# Main.net
KiCad netlist of a schematic drawn in Altium Designer
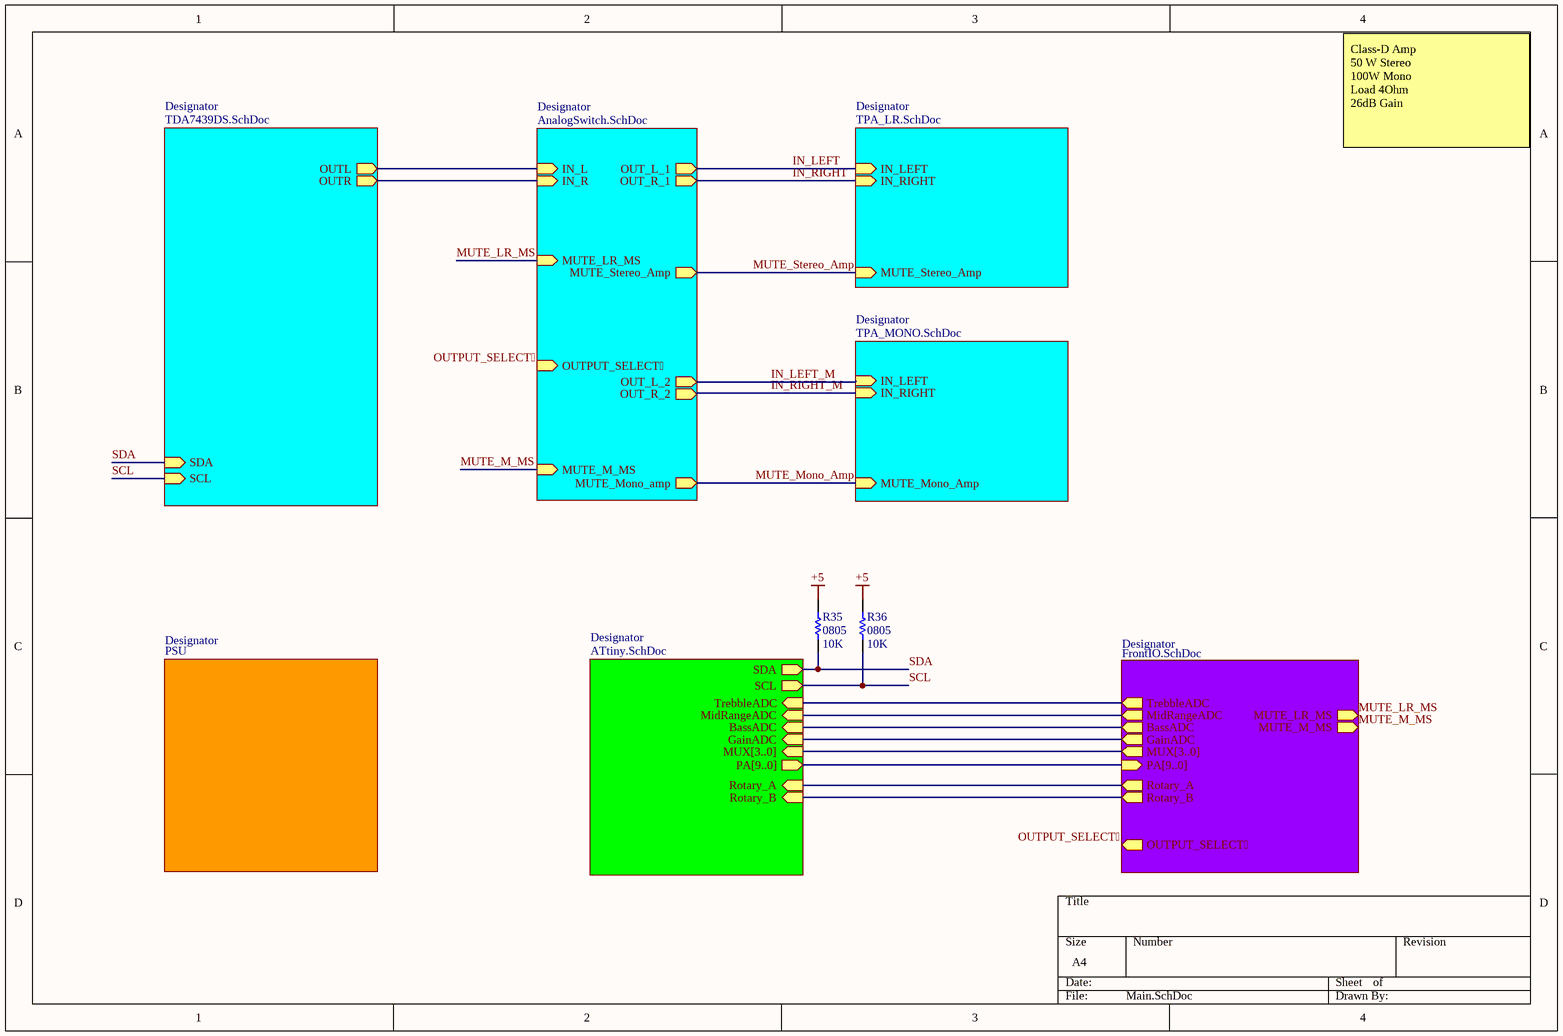
[diagram p0: Main.SchDoc]

(export (version "E")
  (design (tool "Eeschema 10.0.6"))
  (components
    (comp (ref "R35")
      (value "0805")
      (footprint "6-0805_N")
      (description "Resistor")
      (fields (field (name "ALTIUM_VALUE") "10K") (field (name "PUBLISHER") "Altium Limited"))
      (libsource (lib "Miscellaneous Devices") (part "Res1"))
    )
    (comp (ref "R36")
      (value "0805")
      (footprint "6-0805_N")
      (description "Resistor")
      (fields (field (name "ALTIUM_VALUE") "10K") (field (name "PUBLISHER") "Altium Limited"))
      (libsource (lib "Miscellaneous Devices") (part "Res1"))
    )
  )
  (nets
    (net (code "1") (name "+5") (class "Default")
      (node (ref "R35") (pin "2") (pinfunction "2_2") (pintype "passive"))
      (node (ref "R36") (pin "2") (pinfunction "2_2") (pintype "passive"))
    )
    (net (code "20") (name "/SCL") (class "Default")
      (node (ref "R36") (pin "1") (pinfunction "1_1") (pintype "passive"))
    )
    (net (code "21") (name "/SDA") (class "Default")
      (node (ref "R35") (pin "1") (pinfunction "1_1") (pintype "passive"))
    )
  )
)
